# hvsp2.net
KiCad netlist of a schematic drawn in EAGLE
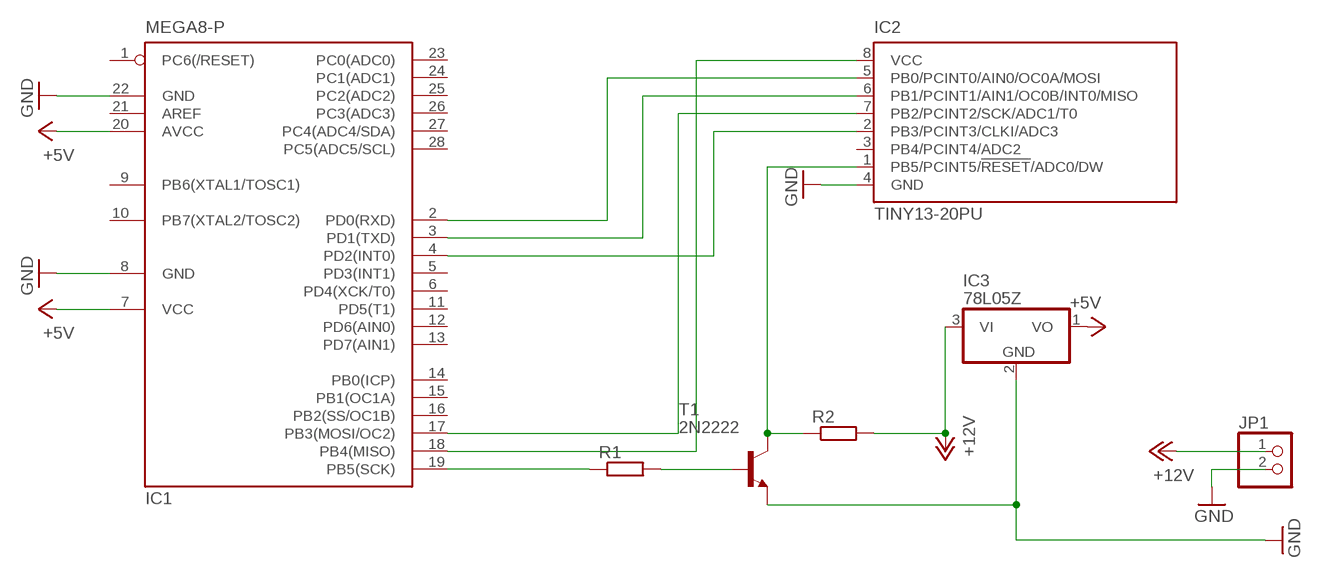
[diagram p0: schematic, sheet 1]

(export (version "E")
  (design (tool "Eeschema 10.0.6"))
  (components
    (comp (ref "IC1")
      (value "MEGA8-P")
      (footprint "eagle-import:DIL28-3")
      (libsource (lib "eagle-import") (part "MEGA8-P"))
    )
    (comp (ref "IC2")
      (value "TINY13-20PU")
      (footprint "eagle-import:DIL08")
      (fields (field (name "MPN") "ATTINY13-20PU"))
      (libsource (lib "eagle-import") (part "TINY13PU-20"))
    )
    (comp (ref "IC3")
      (value "78L05Z")
      (footprint "eagle-import:TO92")
      (libsource (lib "eagle-import") (part "78ZL05"))
    )
    (comp (ref "JP1")
      (value "PINHD-1X2")
      (footprint "eagle-import:1X02")
      (libsource (lib "eagle-import") (part "PINHD-1X2"))
    )
    (comp (ref "R1")
      (value "R-EU_0204/7")
      (footprint "eagle-import:0204_7")
      (libsource (lib "eagle-import") (part "R-EU_0204/7"))
    )
    (comp (ref "R2")
      (value "R-EU_0207/10")
      (footprint "eagle-import:0207_10")
      (libsource (lib "eagle-import") (part "resistor_R-EU_0207/10"))
    )
    (comp (ref "T1")
      (value "2N2222")
      (footprint "eagle-import:TO18")
      (libsource (lib "eagle-import") (part "2N2222"))
    )
  )
  (nets
    (net (code "1") (name "+5V") (class "Default")
      (node (ref "IC1") (pin "20") (pinfunction "AVCC_20") (pintype "power_in"))
      (node (ref "IC1") (pin "7") (pinfunction "VCC_7") (pintype "power_in"))
      (node (ref "IC3") (pin "1") (pinfunction "VO_1") (pintype "passive"))
    )
    (net (code "2") (name "+12V") (class "Default")
      (node (ref "IC3") (pin "3") (pinfunction "VI_3") (pintype "input"))
      (node (ref "JP1") (pin "1") (pinfunction "1_1") (pintype "passive"))
      (node (ref "R2") (pin "2") (pinfunction "2_2") (pintype "passive"))
    )
    (net (code "3") (name "GND") (class "Default")
      (node (ref "IC1") (pin "22") (pinfunction "GND_22") (pintype "power_in"))
      (node (ref "IC1") (pin "8") (pinfunction "GND_8") (pintype "power_in"))
      (node (ref "IC2") (pin "4") (pinfunction "GND_4") (pintype "power_in"))
      (node (ref "IC3") (pin "2") (pinfunction "GND_2") (pintype "passive"))
      (node (ref "JP1") (pin "2") (pinfunction "2_2") (pintype "passive"))
      (node (ref "T1") (pin "1") (pinfunction "E_1") (pintype "passive"))
    )
    (net (code "4") (name "Net-(IC1-PB3(MOSI{slash}OC2))") (class "Default")
      (node (ref "IC1") (pin "17") (pinfunction "PB3(MOSI/OC2)_17") (pintype "bidirectional"))
      (node (ref "IC2") (pin "7") (pinfunction "PB2/PCINT2/SCK/ADC1/T0_7") (pintype "bidirectional"))
    )
    (net (code "5") (name "Net-(IC1-PB4(MISO))") (class "Default")
      (node (ref "IC1") (pin "18") (pinfunction "PB4(MISO)_18") (pintype "bidirectional"))
      (node (ref "IC2") (pin "8") (pinfunction "VCC_8") (pintype "power_in"))
    )
    (net (code "6") (name "Net-(IC1-PB5(SCK))") (class "Default")
      (node (ref "IC1") (pin "19") (pinfunction "PB5(SCK)_19") (pintype "bidirectional"))
      (node (ref "R1") (pin "1") (pinfunction "1_1") (pintype "passive"))
    )
    (net (code "7") (name "Net-(IC1-PD0(RXD))") (class "Default")
      (node (ref "IC1") (pin "2") (pinfunction "PD0(RXD)_2") (pintype "bidirectional"))
      (node (ref "IC2") (pin "5") (pinfunction "PB0/PCINT0/AIN0/OC0A/MOSI_5") (pintype "bidirectional"))
    )
    (net (code "8") (name "Net-(IC1-PD1(TXD))") (class "Default")
      (node (ref "IC1") (pin "3") (pinfunction "PD1(TXD)_3") (pintype "bidirectional"))
      (node (ref "IC2") (pin "6") (pinfunction "PB1/PCINT1/AIN1/OC0B/INT0/MISO_6") (pintype "bidirectional"))
    )
    (net (code "9") (name "Net-(IC1-PD2(INT0))") (class "Default")
      (node (ref "IC1") (pin "4") (pinfunction "PD2(INT0)_4") (pintype "bidirectional"))
      (node (ref "IC2") (pin "2") (pinfunction "PB3/PCINT3/CLKI/ADC3_2") (pintype "bidirectional"))
    )
    (net (code "10") (name "Net-(IC2-PB5{slash}PCINT5{slash}~{RESET}{slash}ADC0{slash}DW)") (class "Default")
      (node (ref "IC2") (pin "1") (pinfunction "PB5/PCINT5/~{RESET}/ADC0/DW_1") (pintype "bidirectional"))
      (node (ref "R2") (pin "1") (pinfunction "1_1") (pintype "passive"))
      (node (ref "T1") (pin "3") (pinfunction "C_3") (pintype "passive"))
    )
    (net (code "11") (name "Net-(T1-B)") (class "Default")
      (node (ref "R1") (pin "2") (pinfunction "2_2") (pintype "passive"))
      (node (ref "T1") (pin "2") (pinfunction "B_2") (pintype "passive"))
    )
    (net (code "12") (name "unconnected-(IC1-AREF-Pad21)") (class "Default")
      (node (ref "IC1") (pin "21") (pinfunction "AREF_21") (pintype "passive"))
    )
    (net (code "13") (name "unconnected-(IC1-PB0(ICP)-Pad14)") (class "Default")
      (node (ref "IC1") (pin "14") (pinfunction "PB0(ICP)_14") (pintype "bidirectional"))
    )
    (net (code "14") (name "unconnected-(IC1-PB1(OC1A)-Pad15)") (class "Default")
      (node (ref "IC1") (pin "15") (pinfunction "PB1(OC1A)_15") (pintype "bidirectional"))
    )
    (net (code "15") (name "unconnected-(IC1-PB2(SS{slash}OC1B)-Pad16)") (class "Default")
      (node (ref "IC1") (pin "16") (pinfunction "PB2(SS/OC1B)_16") (pintype "bidirectional"))
    )
    (net (code "16") (name "unconnected-(IC1-PB6(XTAL1{slash}TOSC1)-Pad9)") (class "Default")
      (node (ref "IC1") (pin "9") (pinfunction "PB6(XTAL1/TOSC1)_9") (pintype "bidirectional"))
    )
    (net (code "17") (name "unconnected-(IC1-PB7(XTAL2{slash}TOSC2)-Pad10)") (class "Default")
      (node (ref "IC1") (pin "10") (pinfunction "PB7(XTAL2/TOSC2)_10") (pintype "bidirectional"))
    )
    (net (code "18") (name "unconnected-(IC1-PC0(ADC0)-Pad23)") (class "Default")
      (node (ref "IC1") (pin "23") (pinfunction "PC0(ADC0)_23") (pintype "bidirectional"))
    )
    (net (code "19") (name "unconnected-(IC1-PC1(ADC1)-Pad24)") (class "Default")
      (node (ref "IC1") (pin "24") (pinfunction "PC1(ADC1)_24") (pintype "bidirectional"))
    )
    (net (code "20") (name "unconnected-(IC1-PC2(ADC2)-Pad25)") (class "Default")
      (node (ref "IC1") (pin "25") (pinfunction "PC2(ADC2)_25") (pintype "bidirectional"))
    )
    (net (code "21") (name "unconnected-(IC1-PC3(ADC3)-Pad26)") (class "Default")
      (node (ref "IC1") (pin "26") (pinfunction "PC3(ADC3)_26") (pintype "bidirectional"))
    )
    (net (code "22") (name "unconnected-(IC1-PC4(ADC4{slash}SDA)-Pad27)") (class "Default")
      (node (ref "IC1") (pin "27") (pinfunction "PC4(ADC4/SDA)_27") (pintype "bidirectional"))
    )
    (net (code "23") (name "unconnected-(IC1-PC5(ADC5{slash}SCL)-Pad28)") (class "Default")
      (node (ref "IC1") (pin "28") (pinfunction "PC5(ADC5/SCL)_28") (pintype "bidirectional"))
    )
    (net (code "24") (name "unconnected-(IC1-PC6({slash}RESET)-Pad1)") (class "Default")
      (node (ref "IC1") (pin "1") (pinfunction "PC6(/RESET)_1") (pintype "bidirectional"))
    )
    (net (code "25") (name "unconnected-(IC1-PD3(INT1)-Pad5)") (class "Default")
      (node (ref "IC1") (pin "5") (pinfunction "PD3(INT1)_5") (pintype "bidirectional"))
    )
    (net (code "26") (name "unconnected-(IC1-PD4(XCK{slash}T0)-Pad6)") (class "Default")
      (node (ref "IC1") (pin "6") (pinfunction "PD4(XCK/T0)_6") (pintype "bidirectional"))
    )
    (net (code "27") (name "unconnected-(IC1-PD5(T1)-Pad11)") (class "Default")
      (node (ref "IC1") (pin "11") (pinfunction "PD5(T1)_11") (pintype "bidirectional"))
    )
    (net (code "28") (name "unconnected-(IC1-PD6(AIN0)-Pad12)") (class "Default")
      (node (ref "IC1") (pin "12") (pinfunction "PD6(AIN0)_12") (pintype "bidirectional"))
    )
    (net (code "29") (name "unconnected-(IC1-PD7(AIN1)-Pad13)") (class "Default")
      (node (ref "IC1") (pin "13") (pinfunction "PD7(AIN1)_13") (pintype "bidirectional"))
    )
    (net (code "30") (name "unconnected-(IC2-PB4{slash}PCINT4{slash}ADC2-Pad3)") (class "Default")
      (node (ref "IC2") (pin "3") (pinfunction "PB4/PCINT4/ADC2_3") (pintype "bidirectional"))
    )
  )
)
